# 6-pin-breakout.net
KiCad netlist of a schematic drawn in EAGLE
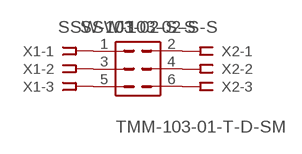
[diagram p0: schematic, sheet 1]

(export (version "E")
  (design (tool "Eeschema 10.0.6"))
  (components
    (comp (ref "J1")
      (value "TMM-103-01-T-D-SM")
      (footprint "eagle-import:2MM-SMD-HEADER-2X3")
      (libsource (lib "eagle-import") (part "TMM-103-01-T-D-SM"))
    )
    (comp (ref "X1")
      (value "SSW-103-02-S-S")
      (footprint "eagle-import:SSW-103-02-S-S")
      (libsource (lib "eagle-import") (part "SSW-103-02-S-S"))
    )
    (comp (ref "X2")
      (value "SSW-103-02-S-S")
      (footprint "eagle-import:SSW-103-02-S-S")
      (libsource (lib "eagle-import") (part "SSW-103-02-S-S"))
    )
  )
  (nets
    (net (code "1") (name "Net-(J1-Pad1)") (class "Default")
      (node (ref "J1") (pin "1") (pinfunction "1_1") (pintype "passive"))
      (node (ref "X1") (pin "1") (pinfunction "1_1") (pintype "passive"))
    )
    (net (code "2") (name "Net-(J1-Pad2)") (class "Default")
      (node (ref "J1") (pin "2") (pinfunction "2_2") (pintype "passive"))
      (node (ref "X2") (pin "1") (pinfunction "1_1") (pintype "passive"))
    )
    (net (code "3") (name "Net-(X1B-1)") (class "Default")
      (node (ref "J1") (pin "3") (pinfunction "3_3") (pintype "passive"))
      (node (ref "X1") (pin "2") (pinfunction "1_2") (pintype "passive"))
    )
    (net (code "4") (name "Net-(X1C-1)") (class "Default")
      (node (ref "J1") (pin "5") (pinfunction "5_5") (pintype "passive"))
      (node (ref "X1") (pin "3") (pinfunction "1_3") (pintype "passive"))
    )
    (net (code "5") (name "Net-(X2B-1)") (class "Default")
      (node (ref "J1") (pin "4") (pinfunction "4_4") (pintype "passive"))
      (node (ref "X2") (pin "2") (pinfunction "1_2") (pintype "passive"))
    )
    (net (code "6") (name "Net-(X2C-1)") (class "Default")
      (node (ref "J1") (pin "6") (pinfunction "6_6") (pintype "passive"))
      (node (ref "X2") (pin "3") (pinfunction "1_3") (pintype "passive"))
    )
  )
)
